# awg-buffer-mod1.net
KiCad netlist of a schematic drawn in EAGLE
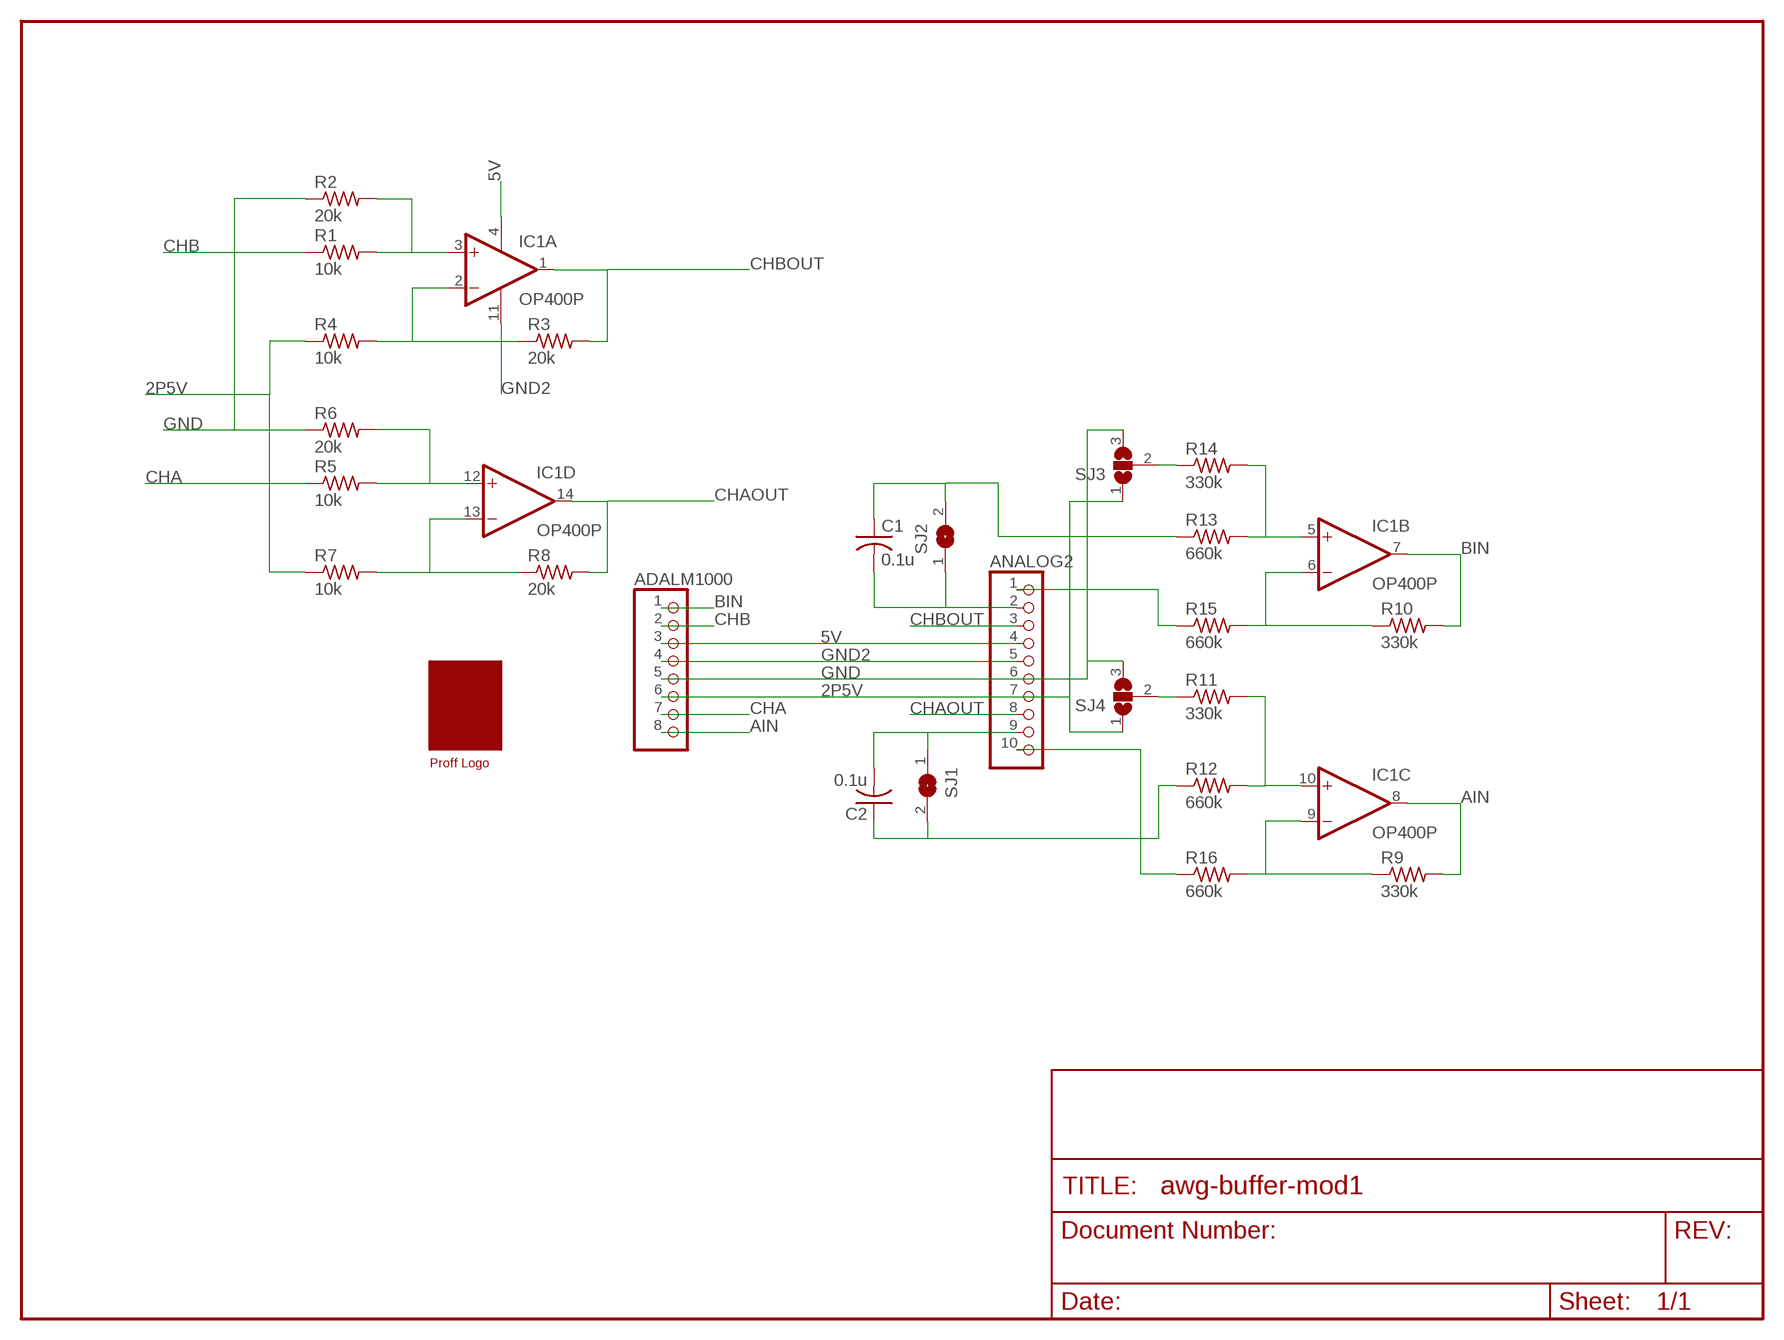
[diagram p0: schematic, sheet 1]

(export (version "E")
  (design (tool "Eeschema 10.0.6"))
  (components
    (comp (ref "ADALM1000")
      (value "PINHD-1X8")
      (footprint "eagle-import:1X08")
      (libsource (lib "eagle-import") (part "PINHD-1X8"))
    )
    (comp (ref "ANALOG2")
      (value "PINHD-1X10")
      (footprint "eagle-import:1X10")
      (libsource (lib "eagle-import") (part "PINHD-1X10"))
    )
    (comp (ref "C1")
      (value "0.1u")
      (footprint "eagle-import:C050-024X044")
      (libsource (lib "eagle-import") (part "C-US050-024X044"))
    )
    (comp (ref "C2")
      (value "0.1u")
      (footprint "eagle-import:C050-024X044")
      (libsource (lib "eagle-import") (part "C-US050-024X044"))
    )
    (comp (ref "IC1")
      (value "OP400P")
      (footprint "eagle-import:DIL14")
      (libsource (lib "eagle-import") (part "OP400P"))
    )
    (comp (ref "R1")
      (value "10k")
      (footprint "eagle-import:0204_7")
      (libsource (lib "eagle-import") (part "R-US_0204/7"))
    )
    (comp (ref "R2")
      (value "20k")
      (footprint "eagle-import:0204_7")
      (libsource (lib "eagle-import") (part "R-US_0204/7"))
    )
    (comp (ref "R3")
      (value "20k")
      (footprint "eagle-import:0204_7")
      (libsource (lib "eagle-import") (part "R-US_0204/7"))
    )
    (comp (ref "R4")
      (value "10k")
      (footprint "eagle-import:0204_7")
      (libsource (lib "eagle-import") (part "R-US_0204/7"))
    )
    (comp (ref "R5")
      (value "10k")
      (footprint "eagle-import:0204_7")
      (libsource (lib "eagle-import") (part "R-US_0204/7"))
    )
    (comp (ref "R6")
      (value "20k")
      (footprint "eagle-import:0204_7")
      (libsource (lib "eagle-import") (part "R-US_0204/7"))
    )
    (comp (ref "R7")
      (value "10k")
      (footprint "eagle-import:0204_7")
      (libsource (lib "eagle-import") (part "R-US_0204/7"))
    )
    (comp (ref "R8")
      (value "20k")
      (footprint "eagle-import:0204_7")
      (libsource (lib "eagle-import") (part "R-US_0204/7"))
    )
    (comp (ref "R9")
      (value "330k")
      (footprint "eagle-import:0204_7")
      (libsource (lib "eagle-import") (part "R-US_0204/7"))
    )
    (comp (ref "R10")
      (value "330k")
      (footprint "eagle-import:0204_7")
      (libsource (lib "eagle-import") (part "R-US_0204/7"))
    )
    (comp (ref "R11")
      (value "330k")
      (footprint "eagle-import:0204_7")
      (libsource (lib "eagle-import") (part "R-US_0204/7"))
    )
    (comp (ref "R12")
      (value "660k")
      (footprint "eagle-import:0204_7")
      (libsource (lib "eagle-import") (part "R-US_0204/7"))
    )
    (comp (ref "R13")
      (value "660k")
      (footprint "eagle-import:0204_7")
      (libsource (lib "eagle-import") (part "R-US_0204/7"))
    )
    (comp (ref "R14")
      (value "330k")
      (footprint "eagle-import:0204_7")
      (libsource (lib "eagle-import") (part "R-US_0204/7"))
    )
    (comp (ref "R15")
      (value "660k")
      (footprint "eagle-import:0204_7")
      (libsource (lib "eagle-import") (part "R-US_0204/7"))
    )
    (comp (ref "R16")
      (value "660k")
      (footprint "eagle-import:0204_7")
      (libsource (lib "eagle-import") (part "R-US_0204/7"))
    )
    (comp (ref "SJ1") (value "SJ") (footprint "eagle-import:SJ") (libsource (lib "eagle-import") (part "SJ")))
    (comp (ref "SJ2") (value "SJ") (footprint "eagle-import:SJ") (libsource (lib "eagle-import") (part "SJ")))
    (comp (ref "SJ3")
      (value "SJ2W")
      (footprint "eagle-import:SJ_2")
      (libsource (lib "eagle-import") (part "SJ2W"))
    )
    (comp (ref "SJ4")
      (value "SJ2W")
      (footprint "eagle-import:SJ_2")
      (libsource (lib "eagle-import") (part "SJ2W"))
    )
    (comp (ref "U$1")
      (value "PROFF")
      (footprint "eagle-import:PROFF")
      (libsource (lib "eagle-import") (part "PROFF"))
    )
  )
  (nets
    (net (code "1") (name "/2P5V") (class "Default")
      (node (ref "ADALM1000") (pin "6") (pinfunction "6_6") (pintype "passive"))
      (node (ref "ANALOG2") (pin "7") (pinfunction "7_7") (pintype "passive"))
      (node (ref "R4") (pin "1") (pinfunction "1_1") (pintype "passive"))
      (node (ref "R7") (pin "1") (pinfunction "1_1") (pintype "passive"))
      (node (ref "SJ3") (pin "1") (pinfunction "1_1") (pintype "passive"))
      (node (ref "SJ4") (pin "1") (pinfunction "1_1") (pintype "passive"))
    )
    (net (code "2") (name "/5V") (class "Default")
      (node (ref "ADALM1000") (pin "3") (pinfunction "3_3") (pintype "passive"))
      (node (ref "ANALOG2") (pin "4") (pinfunction "4_4") (pintype "passive"))
      (node (ref "IC1") (pin "4") (pinfunction "V+_4") (pintype "power_in"))
    )
    (net (code "3") (name "/AIN") (class "Default")
      (node (ref "ADALM1000") (pin "8") (pinfunction "8_8") (pintype "passive"))
      (node (ref "IC1") (pin "8") (pinfunction "OUT_8") (pintype "output"))
      (node (ref "R9") (pin "2") (pinfunction "2_2") (pintype "passive"))
    )
    (net (code "4") (name "/BIN") (class "Default")
      (node (ref "ADALM1000") (pin "1") (pinfunction "1_1") (pintype "passive"))
      (node (ref "IC1") (pin "7") (pinfunction "OUT_7") (pintype "output"))
      (node (ref "R10") (pin "2") (pinfunction "2_2") (pintype "passive"))
    )
    (net (code "5") (name "/CHA") (class "Default")
      (node (ref "ADALM1000") (pin "7") (pinfunction "7_7") (pintype "passive"))
      (node (ref "R5") (pin "1") (pinfunction "1_1") (pintype "passive"))
    )
    (net (code "6") (name "/CHAOUT") (class "Default")
      (node (ref "ANALOG2") (pin "8") (pinfunction "8_8") (pintype "passive"))
      (node (ref "IC1") (pin "14") (pinfunction "OUT_14") (pintype "output"))
      (node (ref "R8") (pin "2") (pinfunction "2_2") (pintype "passive"))
    )
    (net (code "7") (name "/CHB") (class "Default")
      (node (ref "ADALM1000") (pin "2") (pinfunction "2_2") (pintype "passive"))
      (node (ref "R1") (pin "1") (pinfunction "1_1") (pintype "passive"))
    )
    (net (code "8") (name "/CHBOUT") (class "Default")
      (node (ref "ANALOG2") (pin "3") (pinfunction "3_3") (pintype "passive"))
      (node (ref "IC1") (pin "1") (pinfunction "OUT_1") (pintype "output"))
      (node (ref "R3") (pin "2") (pinfunction "2_2") (pintype "passive"))
    )
    (net (code "9") (name "/GND") (class "Default")
      (node (ref "ADALM1000") (pin "5") (pinfunction "5_5") (pintype "passive"))
      (node (ref "ANALOG2") (pin "6") (pinfunction "6_6") (pintype "passive"))
      (node (ref "R2") (pin "1") (pinfunction "1_1") (pintype "passive"))
      (node (ref "R6") (pin "1") (pinfunction "1_1") (pintype "passive"))
      (node (ref "SJ3") (pin "3") (pinfunction "3_3") (pintype "passive"))
      (node (ref "SJ4") (pin "3") (pinfunction "3_3") (pintype "passive"))
    )
    (net (code "10") (name "/GND2") (class "Default")
      (node (ref "ADALM1000") (pin "4") (pinfunction "4_4") (pintype "passive"))
      (node (ref "ANALOG2") (pin "5") (pinfunction "5_5") (pintype "passive"))
      (node (ref "IC1") (pin "11") (pinfunction "V-_11") (pintype "power_in"))
    )
    (net (code "11") (name "Net-(ANALOG2-Pad1)") (class "Default")
      (node (ref "ANALOG2") (pin "1") (pinfunction "1_1") (pintype "passive"))
      (node (ref "R15") (pin "1") (pinfunction "1_1") (pintype "passive"))
    )
    (net (code "12") (name "Net-(ANALOG2-Pad2)") (class "Default")
      (node (ref "ANALOG2") (pin "2") (pinfunction "2_2") (pintype "passive"))
      (node (ref "C1") (pin "2") (pinfunction "2_2") (pintype "passive"))
      (node (ref "SJ2") (pin "1") (pinfunction "1_1") (pintype "passive"))
    )
    (net (code "13") (name "Net-(ANALOG2-Pad9)") (class "Default")
      (node (ref "ANALOG2") (pin "9") (pinfunction "9_9") (pintype "passive"))
      (node (ref "C2") (pin "2") (pinfunction "2_2") (pintype "passive"))
      (node (ref "SJ1") (pin "1") (pinfunction "1_1") (pintype "passive"))
    )
    (net (code "14") (name "Net-(ANALOG2-Pad10)") (class "Default")
      (node (ref "ANALOG2") (pin "10") (pinfunction "10_10") (pintype "passive"))
      (node (ref "R16") (pin "1") (pinfunction "1_1") (pintype "passive"))
    )
    (net (code "15") (name "Net-(C1-Pad1)") (class "Default")
      (node (ref "C1") (pin "1") (pinfunction "1_1") (pintype "passive"))
      (node (ref "R13") (pin "1") (pinfunction "1_1") (pintype "passive"))
      (node (ref "SJ2") (pin "2") (pinfunction "2_2") (pintype "passive"))
    )
    (net (code "16") (name "Net-(C2-Pad1)") (class "Default")
      (node (ref "C2") (pin "1") (pinfunction "1_1") (pintype "passive"))
      (node (ref "R12") (pin "1") (pinfunction "1_1") (pintype "passive"))
      (node (ref "SJ1") (pin "2") (pinfunction "2_2") (pintype "passive"))
    )
    (net (code "17") (name "Net-(IC1A-+IN)") (class "Default")
      (node (ref "IC1") (pin "3") (pinfunction "+IN_3") (pintype "input"))
      (node (ref "R1") (pin "2") (pinfunction "2_2") (pintype "passive"))
      (node (ref "R2") (pin "2") (pinfunction "2_2") (pintype "passive"))
    )
    (net (code "18") (name "Net-(IC1A--IN)") (class "Default")
      (node (ref "IC1") (pin "2") (pinfunction "-IN_2") (pintype "input"))
      (node (ref "R3") (pin "1") (pinfunction "1_1") (pintype "passive"))
      (node (ref "R4") (pin "2") (pinfunction "2_2") (pintype "passive"))
    )
    (net (code "19") (name "Net-(IC1B-+IN)") (class "Default")
      (node (ref "IC1") (pin "5") (pinfunction "+IN_5") (pintype "input"))
      (node (ref "R13") (pin "2") (pinfunction "2_2") (pintype "passive"))
      (node (ref "R14") (pin "2") (pinfunction "2_2") (pintype "passive"))
    )
    (net (code "20") (name "Net-(IC1B--IN)") (class "Default")
      (node (ref "IC1") (pin "6") (pinfunction "-IN_6") (pintype "input"))
      (node (ref "R10") (pin "1") (pinfunction "1_1") (pintype "passive"))
      (node (ref "R15") (pin "2") (pinfunction "2_2") (pintype "passive"))
    )
    (net (code "21") (name "Net-(IC1C-+IN)") (class "Default")
      (node (ref "IC1") (pin "10") (pinfunction "+IN_10") (pintype "input"))
      (node (ref "R11") (pin "2") (pinfunction "2_2") (pintype "passive"))
      (node (ref "R12") (pin "2") (pinfunction "2_2") (pintype "passive"))
    )
    (net (code "22") (name "Net-(IC1C--IN)") (class "Default")
      (node (ref "IC1") (pin "9") (pinfunction "-IN_9") (pintype "input"))
      (node (ref "R16") (pin "2") (pinfunction "2_2") (pintype "passive"))
      (node (ref "R9") (pin "1") (pinfunction "1_1") (pintype "passive"))
    )
    (net (code "23") (name "Net-(IC1D-+IN)") (class "Default")
      (node (ref "IC1") (pin "12") (pinfunction "+IN_12") (pintype "input"))
      (node (ref "R5") (pin "2") (pinfunction "2_2") (pintype "passive"))
      (node (ref "R6") (pin "2") (pinfunction "2_2") (pintype "passive"))
    )
    (net (code "24") (name "Net-(IC1D--IN)") (class "Default")
      (node (ref "IC1") (pin "13") (pinfunction "-IN_13") (pintype "input"))
      (node (ref "R7") (pin "2") (pinfunction "2_2") (pintype "passive"))
      (node (ref "R8") (pin "1") (pinfunction "1_1") (pintype "passive"))
    )
    (net (code "25") (name "Net-(R11-Pad1)") (class "Default")
      (node (ref "R11") (pin "1") (pinfunction "1_1") (pintype "passive"))
      (node (ref "SJ4") (pin "2") (pinfunction "2_2") (pintype "passive"))
    )
    (net (code "26") (name "Net-(R14-Pad1)") (class "Default")
      (node (ref "R14") (pin "1") (pinfunction "1_1") (pintype "passive"))
      (node (ref "SJ3") (pin "2") (pinfunction "2_2") (pintype "passive"))
    )
  )
)
